# fuji_controller_schematic.net
KiCad netlist of a schematic drawn in EAGLE
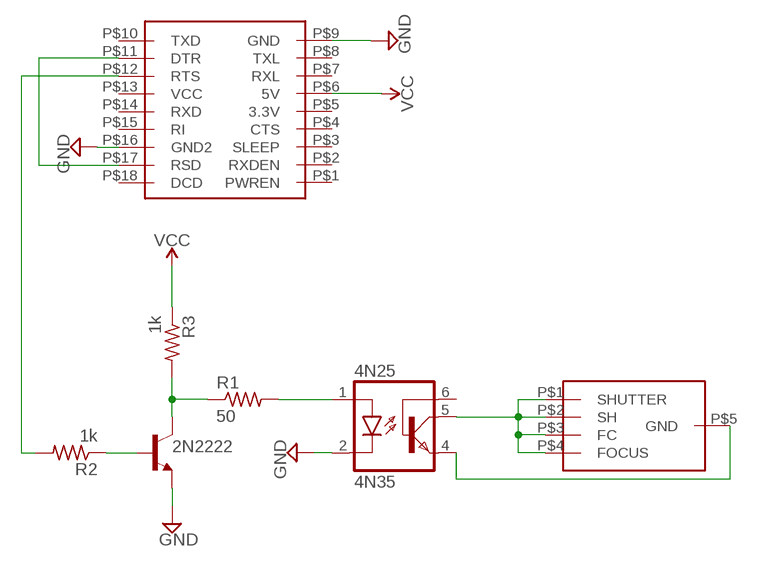
[diagram p0: schematic, sheet 1]

(export (version "E")
  (design (tool "Eeschema 10.0.6"))
  (components
    (comp (ref "2N2222")
      (value "-NPN-TO92-EBC")
      (footprint "eagle-import:TO92-EBC")
      (libsource (lib "eagle-import") (part "-NPN-TO92-EBC"))
    )
    (comp (ref "3.5MM")
      (value "3.5MM_AUDIO_JACK")
      (footprint "eagle-import:3.5MM_AUDIO_JACK")
      (libsource (lib "eagle-import") (part "3.5MM_AUDIO_JACK"))
    )
    (comp (ref "4N25")
      (value "4N35")
      (footprint "eagle-import:DIL06")
      (fields (field (name "MF") "FAIRCHILD SEMICONDUCTOR"))
      (libsource (lib "eagle-import") (part "4N35"))
    )
    (comp (ref "FTDI")
      (value "FTDI_BREAKOUT")
      (footprint "eagle-import:FTDI232_BREAKOUT")
      (libsource (lib "eagle-import") (part "FTDI_BREAKOUT"))
    )
    (comp (ref "R1")
      (value "50")
      (footprint "eagle-import:0204_7")
      (libsource (lib "eagle-import") (part "R-US_0204/7"))
    )
    (comp (ref "R2")
      (value "1k")
      (footprint "eagle-import:0204_7")
      (libsource (lib "eagle-import") (part "R-US_0204/7"))
    )
    (comp (ref "R3")
      (value "1k")
      (footprint "eagle-import:0204_7")
      (libsource (lib "eagle-import") (part "R-US_0204/7"))
    )
  )
  (nets
    (net (code "1") (name "GND") (class "Default")
      (node (ref "2N2222") (pin "E") (pinfunction "E_E") (pintype "passive"))
      (node (ref "4N25") (pin "2") (pinfunction "C_2") (pintype "passive"))
      (node (ref "FTDI") (pin "P$16") (pinfunction "GND2_P$16") (pintype "bidirectional"))
      (node (ref "FTDI") (pin "P$9") (pinfunction "GND_P$9") (pintype "bidirectional"))
    )
    (net (code "2") (name "Net-(2N2222-PadB)") (class "Default")
      (node (ref "2N2222") (pin "B") (pinfunction "B_B") (pintype "passive"))
      (node (ref "R2") (pin "1") (pinfunction "1_1") (pintype "passive"))
    )
    (net (code "3") (name "Net-(2N2222-PadC)") (class "Default")
      (node (ref "2N2222") (pin "C") (pinfunction "C_C") (pintype "passive"))
      (node (ref "R1") (pin "1") (pinfunction "1_1") (pintype "passive"))
      (node (ref "R3") (pin "2") (pinfunction "2_2") (pintype "passive"))
    )
    (net (code "4") (name "Net-(3.5MM-FC)") (class "Default")
      (node (ref "3.5MM") (pin "P$1") (pinfunction "SHUTTER_P$1") (pintype "bidirectional"))
      (node (ref "3.5MM") (pin "P$2") (pinfunction "SH_P$2") (pintype "bidirectional"))
      (node (ref "3.5MM") (pin "P$3") (pinfunction "FC_P$3") (pintype "bidirectional"))
      (node (ref "3.5MM") (pin "P$4") (pinfunction "FOCUS_P$4") (pintype "bidirectional"))
      (node (ref "4N25") (pin "5") (pinfunction "COL_5") (pintype "passive"))
    )
    (net (code "5") (name "Net-(3.5MM-GND)") (class "Default")
      (node (ref "3.5MM") (pin "P$5") (pinfunction "GND_P$5") (pintype "bidirectional"))
      (node (ref "4N25") (pin "4") (pinfunction "EMI_4") (pintype "passive"))
    )
    (net (code "6") (name "Net-(4N25-A)") (class "Default")
      (node (ref "4N25") (pin "1") (pinfunction "A_1") (pintype "passive"))
      (node (ref "R1") (pin "2") (pinfunction "2_2") (pintype "passive"))
    )
    (net (code "7") (name "Net-(FTDI-DTR)") (class "Default")
      (node (ref "FTDI") (pin "P$11") (pinfunction "DTR_P$11") (pintype "bidirectional"))
      (node (ref "FTDI") (pin "P$17") (pinfunction "RSD_P$17") (pintype "bidirectional"))
    )
    (net (code "8") (name "Net-(FTDI-RTS)") (class "Default")
      (node (ref "FTDI") (pin "P$12") (pinfunction "RTS_P$12") (pintype "bidirectional"))
      (node (ref "R2") (pin "2") (pinfunction "2_2") (pintype "passive"))
    )
    (net (code "9") (name "VCC") (class "Default")
      (node (ref "FTDI") (pin "P$6") (pinfunction "5V_P$6") (pintype "bidirectional"))
      (node (ref "R3") (pin "1") (pinfunction "1_1") (pintype "passive"))
    )
    (net (code "10") (name "unconnected-(4N25-BAS-Pad6)") (class "Default")
      (node (ref "4N25") (pin "6") (pinfunction "BAS_6") (pintype "passive"))
    )
    (net (code "11") (name "unconnected-(FTDI-3.3V-PadP$5)") (class "Default")
      (node (ref "FTDI") (pin "P$5") (pinfunction "3.3V_P$5") (pintype "bidirectional"))
    )
    (net (code "12") (name "unconnected-(FTDI-CTS-PadP$4)") (class "Default")
      (node (ref "FTDI") (pin "P$4") (pinfunction "CTS_P$4") (pintype "bidirectional"))
    )
    (net (code "13") (name "unconnected-(FTDI-DCD-PadP$18)") (class "Default")
      (node (ref "FTDI") (pin "P$18") (pinfunction "DCD_P$18") (pintype "bidirectional"))
    )
    (net (code "14") (name "unconnected-(FTDI-PWREN-PadP$1)") (class "Default")
      (node (ref "FTDI") (pin "P$1") (pinfunction "PWREN_P$1") (pintype "bidirectional"))
    )
    (net (code "15") (name "unconnected-(FTDI-RI-PadP$15)") (class "Default")
      (node (ref "FTDI") (pin "P$15") (pinfunction "RI_P$15") (pintype "bidirectional"))
    )
    (net (code "16") (name "unconnected-(FTDI-RXD-PadP$14)") (class "Default")
      (node (ref "FTDI") (pin "P$14") (pinfunction "RXD_P$14") (pintype "bidirectional"))
    )
    (net (code "17") (name "unconnected-(FTDI-RXDEN-PadP$2)") (class "Default")
      (node (ref "FTDI") (pin "P$2") (pinfunction "RXDEN_P$2") (pintype "bidirectional"))
    )
    (net (code "18") (name "unconnected-(FTDI-RXL-PadP$7)") (class "Default")
      (node (ref "FTDI") (pin "P$7") (pinfunction "RXL_P$7") (pintype "bidirectional"))
    )
    (net (code "19") (name "unconnected-(FTDI-SLEEP-PadP$3)") (class "Default")
      (node (ref "FTDI") (pin "P$3") (pinfunction "SLEEP_P$3") (pintype "bidirectional"))
    )
    (net (code "20") (name "unconnected-(FTDI-TXD-PadP$10)") (class "Default")
      (node (ref "FTDI") (pin "P$10") (pinfunction "TXD_P$10") (pintype "bidirectional"))
    )
    (net (code "21") (name "unconnected-(FTDI-TXL-PadP$8)") (class "Default")
      (node (ref "FTDI") (pin "P$8") (pinfunction "TXL_P$8") (pintype "bidirectional"))
    )
    (net (code "22") (name "unconnected-(FTDI-VCC-PadP$13)") (class "Default")
      (node (ref "FTDI") (pin "P$13") (pinfunction "VCC_P$13") (pintype "bidirectional"))
    )
  )
)
